# SCH_Sensor_Gantry_PCB_2022-08-15.net
KiCad netlist of a schematic drawn in EasyEDA
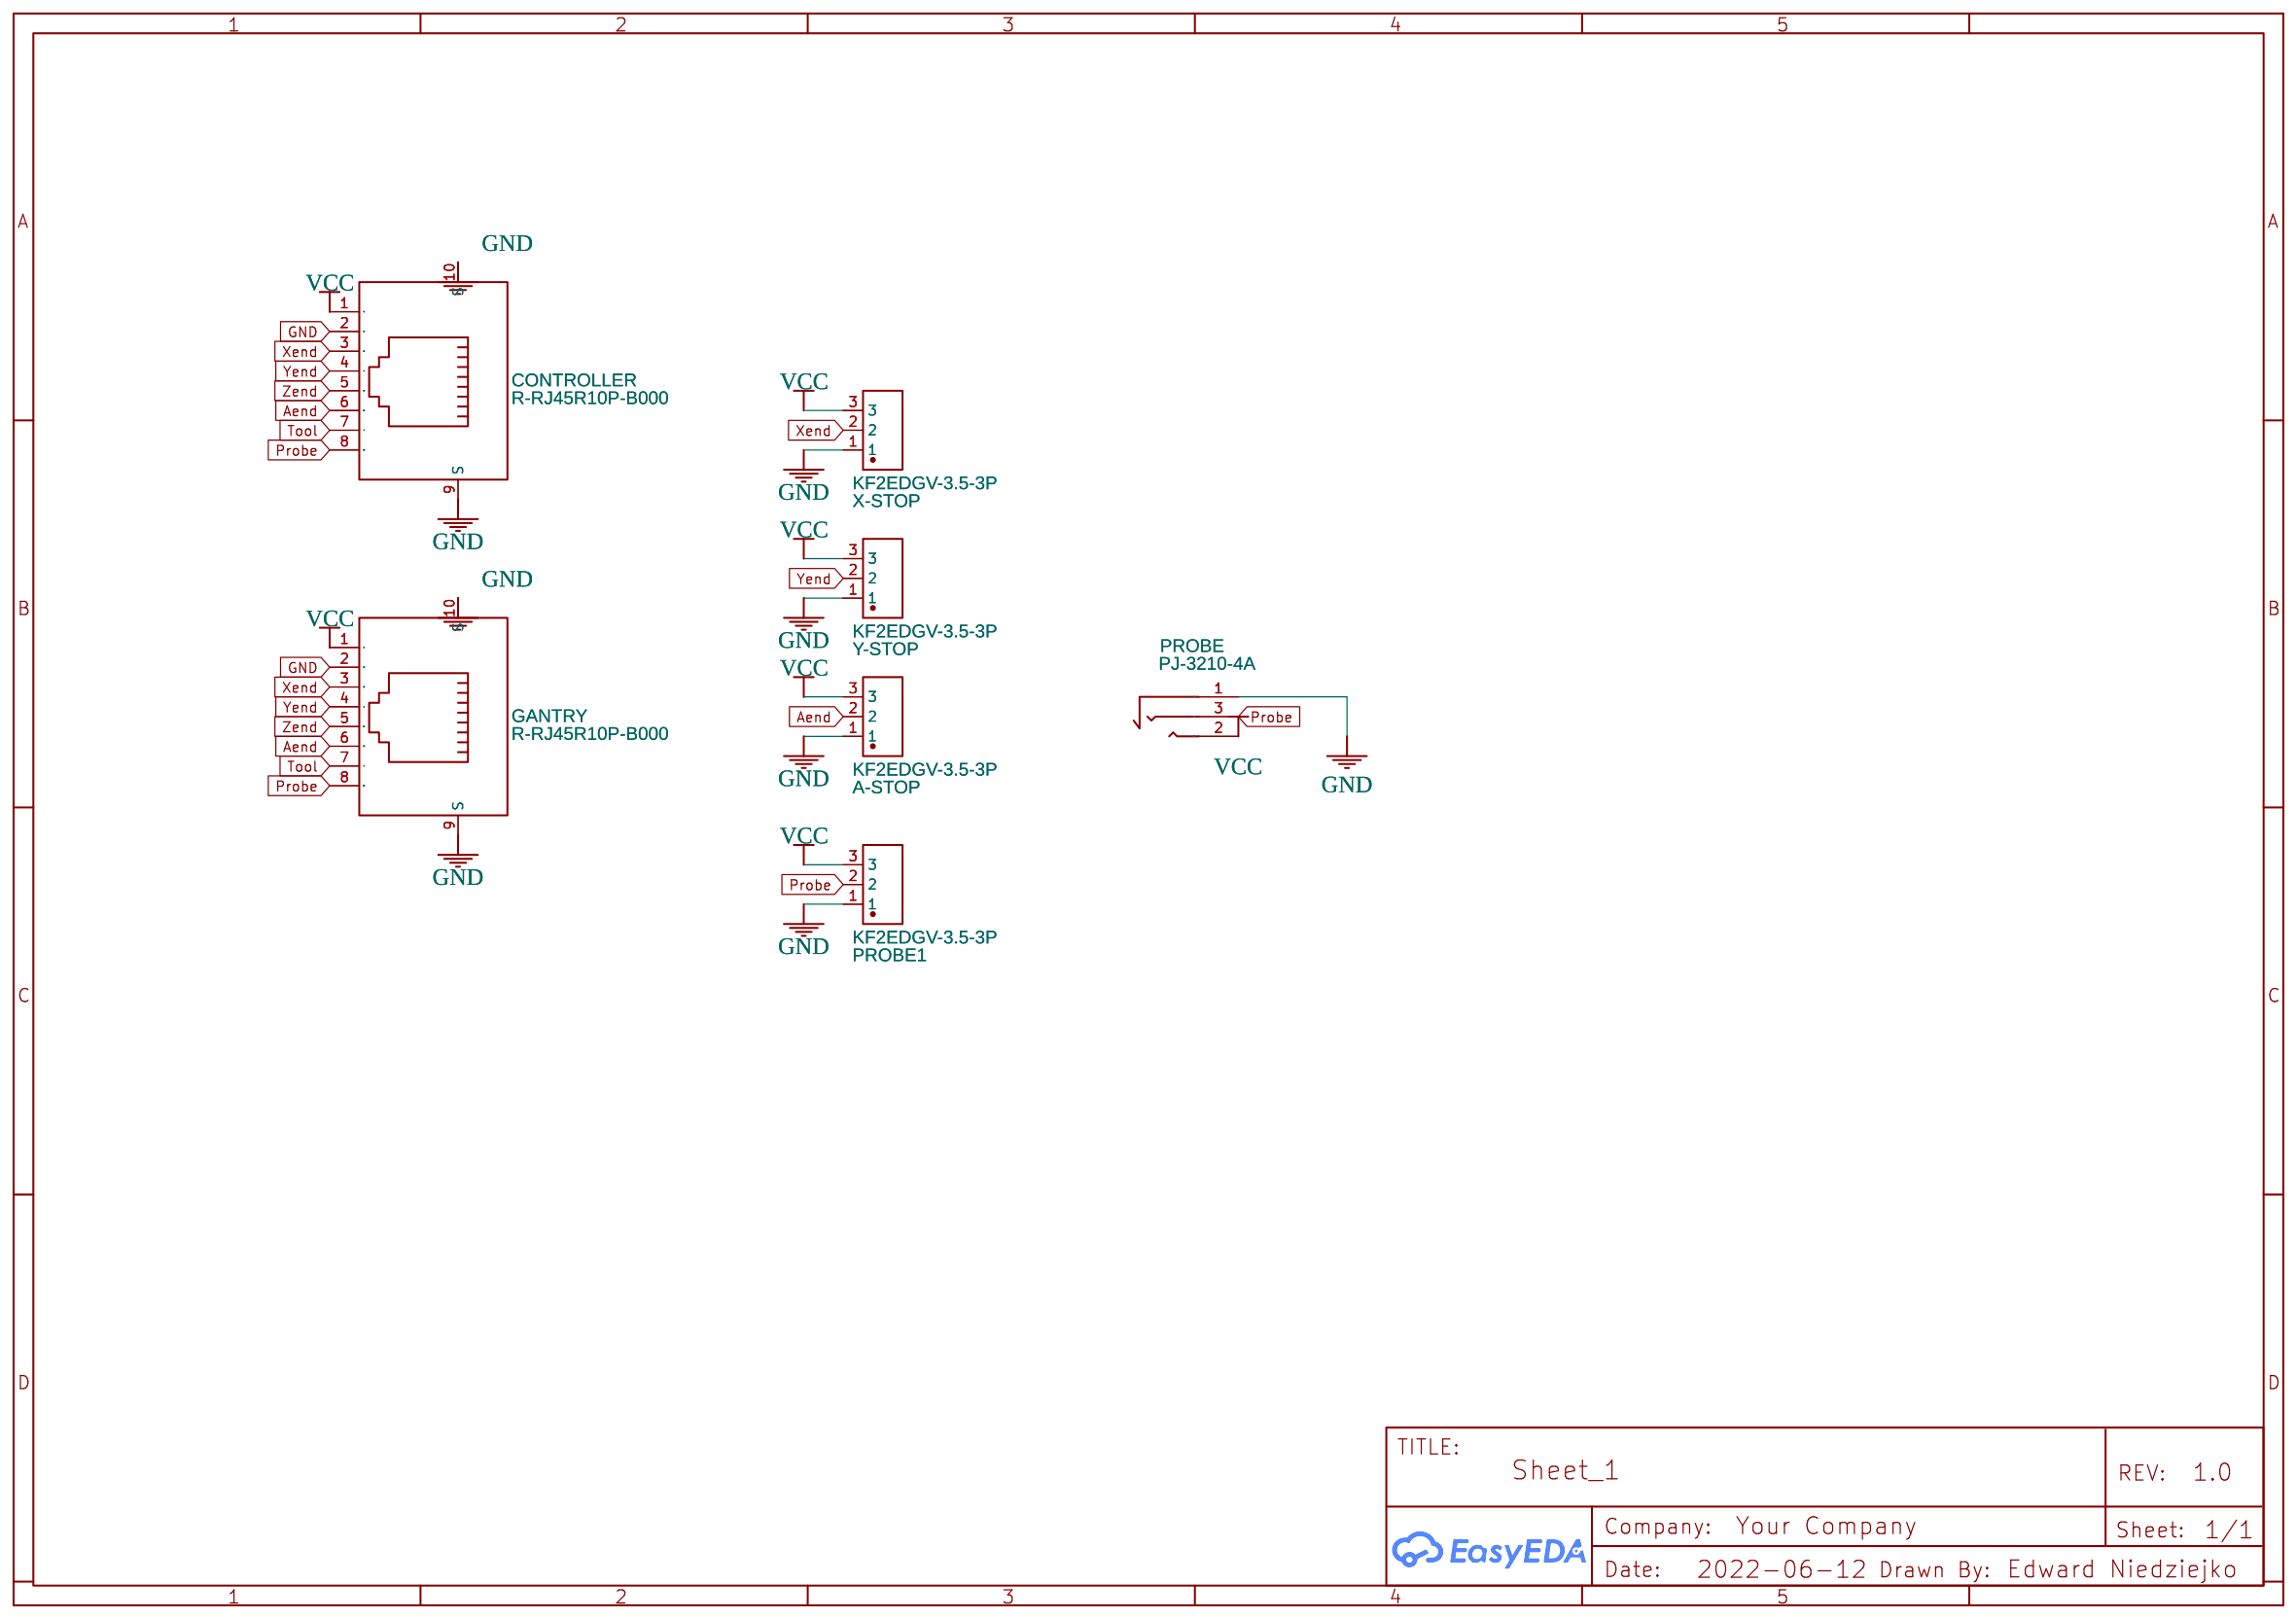
[diagram p0: schematic sheet]

(export (version "E")
  (design (tool "Eeschema 10.0.6"))
  (components
    (comp (ref "A-STOP")
      (value "KF2EDGV-3.5-3P")
      (fields (field (name "BOM_Supplier Part") "C441322"))
      (libsource (lib "") (part "KF2EDGV-3.5-3P"))
    )
    (comp (ref "CONTROLLER")
      (value "R-RJ45R10P-B000")
      (fields (field (name "BOM_Supplier Part") "C386758"))
      (libsource (lib "") (part "R-RJ45R10P-B000_1"))
    )
    (comp (ref "GANTRY")
      (value "R-RJ45R10P-B000")
      (fields (field (name "BOM_Supplier Part") "C386758"))
      (libsource (lib "") (part "R-RJ45R10P-B000"))
    )
    (comp (ref "PROBE")
      (value "PJ-3210-4A")
      (fields (field (name "BOM_Supplier Part") "C136686"))
      (libsource (lib "") (part "PJ-3210-4A"))
    )
    (comp (ref "PROBE1")
      (value "KF2EDGV-3.5-3P")
      (fields (field (name "BOM_Supplier Part") "C441322"))
      (libsource (lib "") (part "KF2EDGV-3.5-3P_2"))
    )
    (comp (ref "X-STOP")
      (value "KF2EDGV-3.5-3P")
      (fields (field (name "BOM_Supplier Part") "C441322"))
      (libsource (lib "") (part "KF2EDGV-3.5-3P_3"))
    )
    (comp (ref "Y-STOP")
      (value "KF2EDGV-3.5-3P")
      (fields (field (name "BOM_Supplier Part") "C441322"))
      (libsource (lib "") (part "KF2EDGV-3.5-3P_1"))
    )
  )
  (nets
    (net (code "1") (name "Aend") (class "Default")
      (node (ref "A-STOP") (pin "2") (pinfunction "2_2") (pintype "unspecified"))
      (node (ref "CONTROLLER") (pin "6") (pinfunction "6_6") (pintype "unspecified"))
      (node (ref "GANTRY") (pin "6") (pinfunction "6_6") (pintype "unspecified"))
    )
    (net (code "2") (name "GND") (class "Default")
      (node (ref "A-STOP") (pin "1") (pinfunction "1_1") (pintype "unspecified"))
      (node (ref "CONTROLLER") (pin "10") (pinfunction "S_10") (pintype "unspecified"))
      (node (ref "CONTROLLER") (pin "2") (pinfunction "2_2") (pintype "unspecified"))
      (node (ref "CONTROLLER") (pin "9") (pinfunction "S_9") (pintype "unspecified"))
      (node (ref "GANTRY") (pin "10") (pinfunction "S_10") (pintype "unspecified"))
      (node (ref "GANTRY") (pin "2") (pinfunction "2_2") (pintype "unspecified"))
      (node (ref "GANTRY") (pin "9") (pinfunction "S_9") (pintype "unspecified"))
      (node (ref "PROBE") (pin "1") (pinfunction "1_1") (pintype "unspecified"))
      (node (ref "PROBE1") (pin "1") (pinfunction "1_1") (pintype "unspecified"))
      (node (ref "X-STOP") (pin "1") (pinfunction "1_1") (pintype "unspecified"))
      (node (ref "Y-STOP") (pin "1") (pinfunction "1_1") (pintype "unspecified"))
    )
    (net (code "3") (name "Probe") (class "Default")
      (node (ref "CONTROLLER") (pin "8") (pinfunction "8_8") (pintype "unspecified"))
      (node (ref "GANTRY") (pin "8") (pinfunction "8_8") (pintype "unspecified"))
      (node (ref "PROBE") (pin "3") (pinfunction "3_3") (pintype "unspecified"))
      (node (ref "PROBE1") (pin "2") (pinfunction "2_2") (pintype "unspecified"))
    )
    (net (code "4") (name "Tool") (class "Default")
      (node (ref "CONTROLLER") (pin "7") (pinfunction "7_7") (pintype "unspecified"))
      (node (ref "GANTRY") (pin "7") (pinfunction "7_7") (pintype "unspecified"))
    )
    (net (code "5") (name "VCC") (class "Default")
      (node (ref "A-STOP") (pin "3") (pinfunction "3_3") (pintype "unspecified"))
      (node (ref "CONTROLLER") (pin "1") (pinfunction "1_1") (pintype "unspecified"))
      (node (ref "GANTRY") (pin "1") (pinfunction "1_1") (pintype "unspecified"))
      (node (ref "PROBE") (pin "2") (pinfunction "2_2") (pintype "unspecified"))
      (node (ref "PROBE1") (pin "3") (pinfunction "3_3") (pintype "unspecified"))
      (node (ref "X-STOP") (pin "3") (pinfunction "3_3") (pintype "unspecified"))
      (node (ref "Y-STOP") (pin "3") (pinfunction "3_3") (pintype "unspecified"))
    )
    (net (code "6") (name "Xend") (class "Default")
      (node (ref "CONTROLLER") (pin "3") (pinfunction "3_3") (pintype "unspecified"))
      (node (ref "GANTRY") (pin "3") (pinfunction "3_3") (pintype "unspecified"))
      (node (ref "X-STOP") (pin "2") (pinfunction "2_2") (pintype "unspecified"))
    )
    (net (code "7") (name "Yend") (class "Default")
      (node (ref "CONTROLLER") (pin "4") (pinfunction "4_4") (pintype "unspecified"))
      (node (ref "GANTRY") (pin "4") (pinfunction "4_4") (pintype "unspecified"))
      (node (ref "Y-STOP") (pin "2") (pinfunction "2_2") (pintype "unspecified"))
    )
    (net (code "8") (name "Zend") (class "Default")
      (node (ref "CONTROLLER") (pin "5") (pinfunction "5_5") (pintype "unspecified"))
      (node (ref "GANTRY") (pin "5") (pinfunction "5_5") (pintype "unspecified"))
    )
  )
)
